# DAC_32CH.net
KiCad netlist of a schematic drawn in Altium Designer
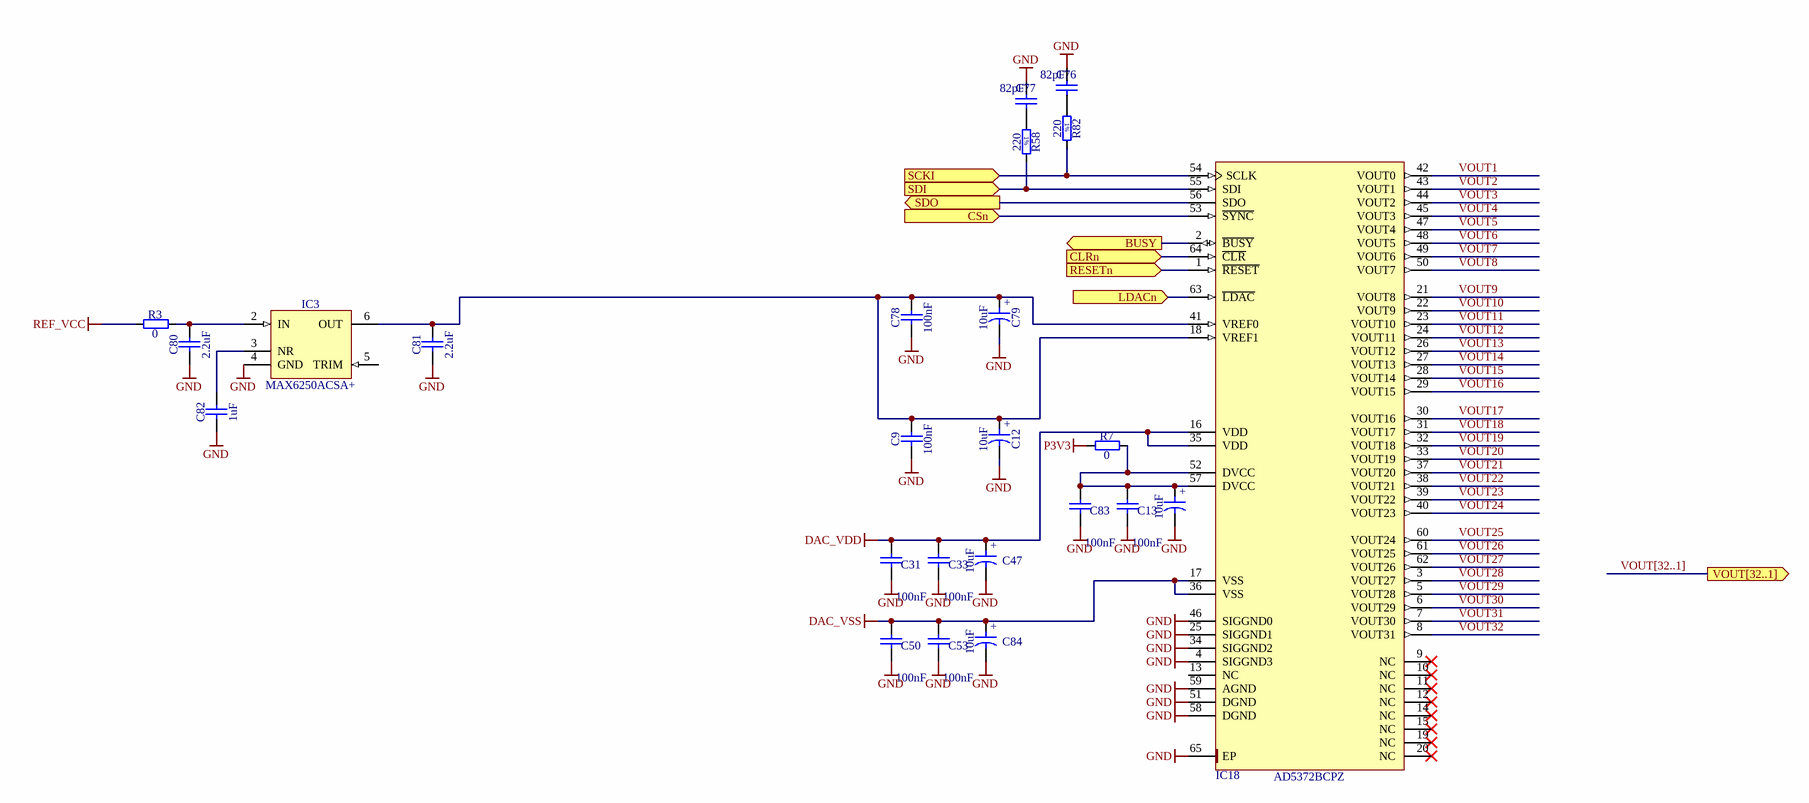
[diagram p0: DAC_32CH.SchDoc]

(export (version "E")
  (design (tool "Eeschema 10.0.6"))
  (components
    (comp (ref "C9")
      (value "100nF")
      (footprint "CAPC1005X55N")
      (description "Non-polarised capacitor")
      (fields
        (field (name "PART NUMBER") "CC0402_100NF_16V_10%_X7R")
        (field (name "VOLTAGE") "16V")
        (field (name "AUTHOR") "CERN DEM JLC")
      )
      (libsource (lib "Capacitors") (part "Capacitor - non polarized"))
    )
    (comp (ref "C12")
      (value "10uF")
      (footprint "CAPMP3216X180N")
      (description "Polarised capacitor")
      (fields
        (field (name "PART NUMBER") "CTE3216-18_10UF_16V_20%_AVX_TCJ")
        (field (name "VOLTAGE") "16V")
        (field (name "AUTHOR") "CERN DEM JLC")
      )
      (libsource (lib "Capacitors") (part "Capacitor - polarized"))
    )
    (comp (ref "C13")
      (value "100nF")
      (footprint "CAPC1005X55N")
      (description "Non-polarised capacitor")
      (fields
        (field (name "PART NUMBER") "CC0402_100NF_16V_10%_X7R")
        (field (name "VOLTAGE") "16V")
        (field (name "AUTHOR") "CERN DEM JLC")
      )
      (libsource (lib "Capacitors") (part "Capacitor - non polarized"))
    )
    (comp (ref "C14")
      (value "10uF")
      (footprint "CAPMP3216X180N")
      (description "Polarised capacitor")
      (fields
        (field (name "PART NUMBER") "CTE3216-18_10UF_16V_20%_AVX_TCJ")
        (field (name "VOLTAGE") "16V")
        (field (name "AUTHOR") "CERN DEM JLC")
      )
      (libsource (lib "Capacitors") (part "Capacitor - polarized"))
    )
    (comp (ref "C31")
      (value "100nF")
      (footprint "CAPC1005X55N")
      (description "Non-polarised capacitor")
      (fields
        (field (name "PART NUMBER") "CC0402_100NF_16V_10%_X7R")
        (field (name "VOLTAGE") "16V")
        (field (name "AUTHOR") "CERN DEM JLC")
      )
      (libsource (lib "Capacitors") (part "Capacitor - non polarized"))
    )
    (comp (ref "C33")
      (value "100nF")
      (footprint "CAPC1005X55N")
      (description "Non-polarised capacitor")
      (fields
        (field (name "PART NUMBER") "CC0402_100NF_16V_10%_X7R")
        (field (name "VOLTAGE") "16V")
        (field (name "AUTHOR") "CERN DEM JLC")
      )
      (libsource (lib "Capacitors") (part "Capacitor - non polarized"))
    )
    (comp (ref "C47")
      (value "10uF")
      (footprint "CAPMP3216X180N")
      (description "Polarised capacitor")
      (fields
        (field (name "PART NUMBER") "CTE3216-18_10UF_16V_20%_AVX_TCJ")
        (field (name "VOLTAGE") "16V")
        (field (name "AUTHOR") "CERN DEM JLC")
      )
      (libsource (lib "Capacitors") (part "Capacitor - polarized"))
    )
    (comp (ref "C50")
      (value "100nF")
      (footprint "CAPC1005X55N")
      (description "Non-polarised capacitor")
      (fields
        (field (name "PART NUMBER") "CC0402_100NF_16V_10%_X7R")
        (field (name "VOLTAGE") "16V")
        (field (name "AUTHOR") "CERN DEM JLC")
      )
      (libsource (lib "Capacitors") (part "Capacitor - non polarized"))
    )
    (comp (ref "C53")
      (value "100nF")
      (footprint "CAPC1005X55N")
      (description "Non-polarised capacitor")
      (fields
        (field (name "PART NUMBER") "CC0402_100NF_16V_10%_X7R")
        (field (name "VOLTAGE") "16V")
        (field (name "AUTHOR") "CERN DEM JLC")
      )
      (libsource (lib "Capacitors") (part "Capacitor - non polarized"))
    )
    (comp (ref "C76")
      (value "82pF")
      (footprint "CAPC1608X87N")
      (description "Non-polarised capacitor")
      (fields
        (field (name "PART NUMBER") "CC0603_82PF_50V_5%_NP0")
        (field (name "VOLTAGE") "50V")
        (field (name "AUTHOR") "CERN DEM JLC")
      )
      (libsource (lib "Capacitors") (part "Capacitor - non polarized"))
    )
    (comp (ref "C77")
      (value "82pF")
      (footprint "CAPC1608X87N")
      (description "Non-polarised capacitor")
      (fields
        (field (name "PART NUMBER") "CC0603_82PF_50V_5%_NP0")
        (field (name "VOLTAGE") "50V")
        (field (name "AUTHOR") "CERN DEM JLC")
      )
      (libsource (lib "Capacitors") (part "Capacitor - non polarized"))
    )
    (comp (ref "C78")
      (value "100nF")
      (footprint "CAPC1005X55N")
      (description "Non-polarised capacitor")
      (fields
        (field (name "PART NUMBER") "CC0402_100NF_16V_10%_X7R")
        (field (name "VOLTAGE") "16V")
        (field (name "AUTHOR") "CERN DEM JLC")
      )
      (libsource (lib "Capacitors") (part "Capacitor - non polarized"))
    )
    (comp (ref "C79")
      (value "10uF")
      (footprint "CAPMP3216X180N")
      (description "Polarised capacitor")
      (fields
        (field (name "PART NUMBER") "CTE3216-18_10UF_16V_20%_AVX_TCJ")
        (field (name "VOLTAGE") "16V")
        (field (name "AUTHOR") "CERN DEM JLC")
      )
      (libsource (lib "Capacitors") (part "Capacitor - polarized"))
    )
    (comp (ref "C80")
      (value "2.2uF")
      (footprint "CAPC1608X87N")
      (description "Non-polarised capacitor")
      (fields
        (field (name "PART NUMBER") "CC0603_2.2UF_16V_10%_X5R")
        (field (name "VOLTAGE") "16V")
        (field (name "AUTHOR") "CERN DEM JLC")
      )
      (libsource (lib "Capacitors") (part "Capacitor - non polarized"))
    )
    (comp (ref "C81")
      (value "2.2uF")
      (footprint "CAPC1608X87N")
      (description "Non-polarised capacitor")
      (fields
        (field (name "PART NUMBER") "CC0603_2.2UF_16V_10%_X5R")
        (field (name "VOLTAGE") "16V")
        (field (name "AUTHOR") "CERN DEM JLC")
      )
      (libsource (lib "Capacitors") (part "Capacitor - non polarized"))
    )
    (comp (ref "C82")
      (value "1uF")
      (footprint "CAPC1608X87N")
      (description "Non-polarised capacitor")
      (fields
        (field (name "PART NUMBER") "CC0603_1UF_25V_10%_X7R")
        (field (name "VOLTAGE") "25V")
        (field (name "AUTHOR") "CERN DEM JLC")
      )
      (libsource (lib "Capacitors") (part "Capacitor - non polarized"))
    )
    (comp (ref "C83")
      (value "100nF")
      (footprint "CAPC1005X55N")
      (description "Non-polarised capacitor")
      (fields
        (field (name "PART NUMBER") "CC0402_100NF_16V_10%_X7R")
        (field (name "VOLTAGE") "16V")
        (field (name "AUTHOR") "CERN DEM JLC")
      )
      (libsource (lib "Capacitors") (part "Capacitor - non polarized"))
    )
    (comp (ref "C84")
      (value "10uF")
      (footprint "CAPMP3216X180N")
      (description "Polarised capacitor")
      (fields
        (field (name "PART NUMBER") "CTE3216-18_10UF_16V_20%_AVX_TCJ")
        (field (name "VOLTAGE") "16V")
        (field (name "AUTHOR") "CERN DEM JLC")
      )
      (libsource (lib "Capacitors") (part "Capacitor - polarized"))
    )
    (comp (ref "IC3")
      (value "MAX6250ACSA+")
      (footprint "SOIC127P600X175-8N")
      (description "1ppm/°C, Low-Noise, Precision, +5.000V Voltage Reference")
      (fields (field (name "MANUFACTURER") "MAXIM") (field (name "AUTHOR") "CERN DEM JMW"))
      (libsource (lib "ICs And Semiconductors") (part "MAX6250"))
    )
    (comp (ref "IC18")
      (value "AD5372BCPZ")
      (footprint "QFN50P900X900X100-65N-S725")
      (description "32-Channel, 16-Bit, Serial Input, Voltage Output Digital-to-Analog Converter")
      (fields (field (name "MANUFACTURER") "ANALOG DEVICES") (field (name "AUTHOR") "GK"))
      (libsource (lib "LIBRARY_SCH") (part "DAC_AD5372"))
    )
    (comp (ref "R3")
      (value "0")
      (footprint "RESC1005X40N")
      (description "Resistor")
      (fields
        (field (name "PART NUMBER") "R0402_0R_JUMPER")
        (field (name "MANUFACTURER") "GENERIC")
        (field (name "AUTHOR") "CERN DEM JLC")
      )
      (libsource (lib "Resistors") (part "Resistor"))
    )
    (comp (ref "R7")
      (value "0")
      (footprint "RESC1005X40N")
      (description "Resistor")
      (fields
        (field (name "PART NUMBER") "R0402_0R_JUMPER")
        (field (name "MANUFACTURER") "GENERIC")
        (field (name "AUTHOR") "CERN DEM JLC")
      )
      (libsource (lib "Resistors") (part "Resistor"))
    )
    (comp (ref "R58")
      (value "220")
      (footprint "RESC1608X55N")
      (description "Resistor - 1%")
      (fields
        (field (name "PART NUMBER") "R0603_220R_1%_0.1W_100PPM")
        (field (name "POWER") "0.1W")
        (field (name "AUTHOR") "CERN DEM JLC")
      )
      (libsource (lib "Resistors") (part "Resistor - 1%"))
    )
    (comp (ref "R82")
      (value "220")
      (footprint "RESC1608X55N")
      (description "Resistor - 1%")
      (fields
        (field (name "PART NUMBER") "R0603_220R_1%_0.1W_100PPM")
        (field (name "POWER") "0.1W")
        (field (name "AUTHOR") "CERN DEM JLC")
      )
      (libsource (lib "Resistors") (part "Resistor - 1%"))
    )
  )
  (nets
    (net (code "1") (name "/BUSY") (class "Default")
      (node (ref "IC18") (pin "2") (pinfunction "~{BUSY}_2") (pintype "bidirectional"))
    )
    (net (code "2") (name "/CLRn") (class "Default")
      (node (ref "IC18") (pin "64") (pinfunction "~{CLR}_64") (pintype "input"))
    )
    (net (code "3") (name "/CSn") (class "Default")
      (node (ref "IC18") (pin "53") (pinfunction "~{SYNC}_53") (pintype "input"))
    )
    (net (code "4") (name "/LDACn") (class "Default")
      (node (ref "IC18") (pin "63") (pinfunction "~{LDAC}_63") (pintype "input"))
    )
    (net (code "5") (name "/RESETn") (class "Default")
      (node (ref "IC18") (pin "1") (pinfunction "~{RESET}_1") (pintype "input"))
    )
    (net (code "6") (name "/SCKI") (class "Default")
      (node (ref "IC18") (pin "54") (pinfunction "SCLK_54") (pintype "input"))
      (node (ref "R82") (pin "2") (pinfunction "2_2") (pintype "passive"))
    )
    (net (code "7") (name "/SDI") (class "Default")
      (node (ref "IC18") (pin "55") (pinfunction "SDI_55") (pintype "input"))
      (node (ref "R58") (pin "2") (pinfunction "2_2") (pintype "passive"))
    )
    (net (code "8") (name "/SDO") (class "Default")
      (node (ref "IC18") (pin "56") (pinfunction "SDO_56") (pintype "tri_state"))
    )
    (net (code "9") (name "/VOUT1") (class "Default")
      (node (ref "IC18") (pin "42") (pinfunction "VOUT0_42") (pintype "output"))
    )
    (net (code "10") (name "/VOUT2") (class "Default")
      (node (ref "IC18") (pin "43") (pinfunction "VOUT1_43") (pintype "output"))
    )
    (net (code "11") (name "/VOUT3") (class "Default")
      (node (ref "IC18") (pin "44") (pinfunction "VOUT2_44") (pintype "output"))
    )
    (net (code "12") (name "/VOUT4") (class "Default")
      (node (ref "IC18") (pin "45") (pinfunction "VOUT3_45") (pintype "output"))
    )
    (net (code "13") (name "/VOUT5") (class "Default")
      (node (ref "IC18") (pin "47") (pinfunction "VOUT4_47") (pintype "output"))
    )
    (net (code "14") (name "/VOUT6") (class "Default")
      (node (ref "IC18") (pin "48") (pinfunction "VOUT5_48") (pintype "output"))
    )
    (net (code "15") (name "/VOUT7") (class "Default")
      (node (ref "IC18") (pin "49") (pinfunction "VOUT6_49") (pintype "output"))
    )
    (net (code "16") (name "/VOUT8") (class "Default")
      (node (ref "IC18") (pin "50") (pinfunction "VOUT7_50") (pintype "output"))
    )
    (net (code "17") (name "/VOUT9") (class "Default")
      (node (ref "IC18") (pin "21") (pinfunction "VOUT8_21") (pintype "output"))
    )
    (net (code "18") (name "/VOUT10") (class "Default")
      (node (ref "IC18") (pin "22") (pinfunction "VOUT9_22") (pintype "output"))
    )
    (net (code "19") (name "/VOUT11") (class "Default")
      (node (ref "IC18") (pin "23") (pinfunction "VOUT10_23") (pintype "output"))
    )
    (net (code "20") (name "/VOUT12") (class "Default")
      (node (ref "IC18") (pin "24") (pinfunction "VOUT11_24") (pintype "output"))
    )
    (net (code "21") (name "/VOUT13") (class "Default")
      (node (ref "IC18") (pin "26") (pinfunction "VOUT12_26") (pintype "output"))
    )
    (net (code "22") (name "/VOUT14") (class "Default")
      (node (ref "IC18") (pin "27") (pinfunction "VOUT13_27") (pintype "output"))
    )
    (net (code "23") (name "/VOUT15") (class "Default")
      (node (ref "IC18") (pin "28") (pinfunction "VOUT14_28") (pintype "output"))
    )
    (net (code "24") (name "/VOUT16") (class "Default")
      (node (ref "IC18") (pin "29") (pinfunction "VOUT15_29") (pintype "output"))
    )
    (net (code "25") (name "/VOUT17") (class "Default")
      (node (ref "IC18") (pin "30") (pinfunction "VOUT16_30") (pintype "output"))
    )
    (net (code "26") (name "/VOUT18") (class "Default")
      (node (ref "IC18") (pin "31") (pinfunction "VOUT17_31") (pintype "output"))
    )
    (net (code "27") (name "/VOUT19") (class "Default")
      (node (ref "IC18") (pin "32") (pinfunction "VOUT18_32") (pintype "output"))
    )
    (net (code "28") (name "/VOUT20") (class "Default")
      (node (ref "IC18") (pin "33") (pinfunction "VOUT19_33") (pintype "output"))
    )
    (net (code "29") (name "/VOUT21") (class "Default")
      (node (ref "IC18") (pin "37") (pinfunction "VOUT20_37") (pintype "output"))
    )
    (net (code "30") (name "/VOUT22") (class "Default")
      (node (ref "IC18") (pin "38") (pinfunction "VOUT21_38") (pintype "output"))
    )
    (net (code "31") (name "/VOUT23") (class "Default")
      (node (ref "IC18") (pin "39") (pinfunction "VOUT22_39") (pintype "output"))
    )
    (net (code "32") (name "/VOUT24") (class "Default")
      (node (ref "IC18") (pin "40") (pinfunction "VOUT23_40") (pintype "output"))
    )
    (net (code "33") (name "/VOUT25") (class "Default")
      (node (ref "IC18") (pin "60") (pinfunction "VOUT24_60") (pintype "output"))
    )
    (net (code "34") (name "/VOUT26") (class "Default")
      (node (ref "IC18") (pin "61") (pinfunction "VOUT25_61") (pintype "output"))
    )
    (net (code "35") (name "/VOUT27") (class "Default")
      (node (ref "IC18") (pin "62") (pinfunction "VOUT26_62") (pintype "output"))
    )
    (net (code "36") (name "/VOUT28") (class "Default")
      (node (ref "IC18") (pin "3") (pinfunction "VOUT27_3") (pintype "output"))
    )
    (net (code "37") (name "/VOUT29") (class "Default")
      (node (ref "IC18") (pin "5") (pinfunction "VOUT28_5") (pintype "output"))
    )
    (net (code "38") (name "/VOUT30") (class "Default")
      (node (ref "IC18") (pin "6") (pinfunction "VOUT29_6") (pintype "output"))
    )
    (net (code "39") (name "/VOUT31") (class "Default")
      (node (ref "IC18") (pin "7") (pinfunction "VOUT30_7") (pintype "output"))
    )
    (net (code "40") (name "/VOUT32") (class "Default")
      (node (ref "IC18") (pin "8") (pinfunction "VOUT31_8") (pintype "output"))
    )
    (net (code "42") (name "DAC_VDD") (class "Default")
      (node (ref "C31") (pin "2") (pinfunction "2_2") (pintype "passive"))
      (node (ref "C33") (pin "2") (pinfunction "2_2") (pintype "passive"))
      (node (ref "C47") (pin "1") (pinfunction "1_1") (pintype "passive"))
      (node (ref "IC18") (pin "16") (pinfunction "VDD_16") (pintype "power_in"))
      (node (ref "IC18") (pin "35") (pinfunction "VDD_35") (pintype "power_in"))
    )
    (net (code "43") (name "DAC_VSS") (class "Default")
      (node (ref "C50") (pin "2") (pinfunction "2_2") (pintype "passive"))
      (node (ref "C53") (pin "2") (pinfunction "2_2") (pintype "passive"))
      (node (ref "C84") (pin "1") (pinfunction "1_1") (pintype "passive"))
      (node (ref "IC18") (pin "17") (pinfunction "VSS_17") (pintype "power_in"))
      (node (ref "IC18") (pin "36") (pinfunction "VSS_36") (pintype "power_in"))
    )
    (net (code "44") (name "GND") (class "Default")
      (node (ref "C12") (pin "2") (pinfunction "2_2") (pintype "passive"))
      (node (ref "C13") (pin "1") (pinfunction "1_1") (pintype "passive"))
      (node (ref "C14") (pin "2") (pinfunction "2_2") (pintype "passive"))
      (node (ref "C31") (pin "1") (pinfunction "1_1") (pintype "passive"))
      (node (ref "C33") (pin "1") (pinfunction "1_1") (pintype "passive"))
      (node (ref "C47") (pin "2") (pinfunction "2_2") (pintype "passive"))
      (node (ref "C50") (pin "1") (pinfunction "1_1") (pintype "passive"))
      (node (ref "C53") (pin "1") (pinfunction "1_1") (pintype "passive"))
      (node (ref "C76") (pin "1") (pinfunction "1_1") (pintype "passive"))
      (node (ref "C77") (pin "1") (pinfunction "1_1") (pintype "passive"))
      (node (ref "C78") (pin "1") (pinfunction "1_1") (pintype "passive"))
      (node (ref "C79") (pin "2") (pinfunction "2_2") (pintype "passive"))
      (node (ref "C80") (pin "1") (pinfunction "1_1") (pintype "passive"))
      (node (ref "C81") (pin "1") (pinfunction "1_1") (pintype "passive"))
      (node (ref "C82") (pin "1") (pinfunction "1_1") (pintype "passive"))
      (node (ref "C83") (pin "1") (pinfunction "1_1") (pintype "passive"))
      (node (ref "C84") (pin "2") (pinfunction "2_2") (pintype "passive"))
      (node (ref "C9") (pin "1") (pinfunction "1_1") (pintype "passive"))
      (node (ref "IC18") (pin "25") (pinfunction "SIGGND1_25") (pintype "power_in"))
      (node (ref "IC18") (pin "34") (pinfunction "SIGGND2_34") (pintype "power_in"))
      (node (ref "IC18") (pin "4") (pinfunction "SIGGND3_4") (pintype "power_in"))
      (node (ref "IC18") (pin "46") (pinfunction "SIGGND0_46") (pintype "power_in"))
      (node (ref "IC18") (pin "51") (pinfunction "DGND_51") (pintype "power_in"))
      (node (ref "IC18") (pin "58") (pinfunction "DGND_58") (pintype "power_in"))
      (node (ref "IC18") (pin "59") (pinfunction "AGND_59") (pintype "power_in"))
      (node (ref "IC18") (pin "65") (pinfunction "EP_65") (pintype "power_in"))
      (node (ref "IC3") (pin "4") (pinfunction "GND_4") (pintype "power_in"))
    )
    (net (code "45") (name "Net-(C13-Pad2)") (class "Default")
      (node (ref "C13") (pin "2") (pinfunction "2_2") (pintype "passive"))
      (node (ref "C14") (pin "1") (pinfunction "1_1") (pintype "passive"))
      (node (ref "C83") (pin "2") (pinfunction "2_2") (pintype "passive"))
      (node (ref "IC18") (pin "52") (pinfunction "DVCC_52") (pintype "power_in"))
      (node (ref "IC18") (pin "57") (pinfunction "DVCC_57") (pintype "power_in"))
      (node (ref "R7") (pin "2") (pinfunction "2_2") (pintype "passive"))
    )
    (net (code "46") (name "Net-(C76-Pad2)") (class "Default")
      (node (ref "C76") (pin "2") (pinfunction "2_2") (pintype "passive"))
      (node (ref "R82") (pin "1") (pinfunction "1_1") (pintype "passive"))
    )
    (net (code "47") (name "Net-(C77-Pad2)") (class "Default")
      (node (ref "C77") (pin "2") (pinfunction "2_2") (pintype "passive"))
      (node (ref "R58") (pin "1") (pinfunction "1_1") (pintype "passive"))
    )
    (net (code "48") (name "Net-(IC3-IN)") (class "Default")
      (node (ref "C80") (pin "2") (pinfunction "2_2") (pintype "passive"))
      (node (ref "IC3") (pin "2") (pinfunction "IN_2") (pintype "input"))
      (node (ref "R3") (pin "2") (pinfunction "2_2") (pintype "passive"))
    )
    (net (code "49") (name "Net-(IC3-NR)") (class "Default")
      (node (ref "C82") (pin "2") (pinfunction "2_2") (pintype "passive"))
      (node (ref "IC3") (pin "3") (pinfunction "NR_3") (pintype "passive"))
    )
    (net (code "50") (name "Net-(IC18-VREF0)") (class "Default")
      (node (ref "C12") (pin "1") (pinfunction "1_1") (pintype "passive"))
      (node (ref "C78") (pin "2") (pinfunction "2_2") (pintype "passive"))
      (node (ref "C79") (pin "1") (pinfunction "1_1") (pintype "passive"))
      (node (ref "C81") (pin "2") (pinfunction "2_2") (pintype "passive"))
      (node (ref "C9") (pin "2") (pinfunction "2_2") (pintype "passive"))
      (node (ref "IC18") (pin "18") (pinfunction "VREF1_18") (pintype "input"))
      (node (ref "IC18") (pin "41") (pinfunction "VREF0_41") (pintype "input"))
      (node (ref "IC3") (pin "6") (pinfunction "OUT_6") (pintype "power_in"))
    )
    (net (code "51") (name "P3V3") (class "Default")
      (node (ref "R7") (pin "1") (pinfunction "1_1") (pintype "passive"))
    )
    (net (code "52") (name "REF_VCC") (class "Default")
      (node (ref "R3") (pin "1") (pinfunction "1_1") (pintype "passive"))
    )
    (net (code "53") (name "unconnected-(IC3-TRIM-Pad5)") (class "Default")
      (node (ref "IC3") (pin "5") (pinfunction "TRIM_5") (pintype "input"))
    )
    (net (code "54") (name "unconnected-(IC18-NC-Pad9)") (class "Default")
      (node (ref "IC18") (pin "9") (pinfunction "NC_9") (pintype "passive+no_connect"))
    )
    (net (code "55") (name "unconnected-(IC18-NC-Pad10)") (class "Default")
      (node (ref "IC18") (pin "10") (pinfunction "NC_10") (pintype "passive+no_connect"))
    )
    (net (code "56") (name "unconnected-(IC18-NC-Pad11)") (class "Default")
      (node (ref "IC18") (pin "11") (pinfunction "NC_11") (pintype "passive+no_connect"))
    )
    (net (code "57") (name "unconnected-(IC18-NC-Pad12)") (class "Default")
      (node (ref "IC18") (pin "12") (pinfunction "NC_12") (pintype "passive+no_connect"))
    )
    (net (code "58") (name "unconnected-(IC18-NC-Pad13)") (class "Default")
      (node (ref "IC18") (pin "13") (pinfunction "NC_13") (pintype "passive"))
    )
    (net (code "59") (name "unconnected-(IC18-NC-Pad14)") (class "Default")
      (node (ref "IC18") (pin "14") (pinfunction "NC_14") (pintype "passive+no_connect"))
    )
    (net (code "60") (name "unconnected-(IC18-NC-Pad15)") (class "Default")
      (node (ref "IC18") (pin "15") (pinfunction "NC_15") (pintype "passive+no_connect"))
    )
    (net (code "61") (name "unconnected-(IC18-NC-Pad19)") (class "Default")
      (node (ref "IC18") (pin "19") (pinfunction "NC_19") (pintype "passive+no_connect"))
    )
    (net (code "62") (name "unconnected-(IC18-NC-Pad20)") (class "Default")
      (node (ref "IC18") (pin "20") (pinfunction "NC_20") (pintype "passive+no_connect"))
    )
  )
)
